# 09-DPLL-3.net
KiCad netlist of a schematic drawn in Altium Designer
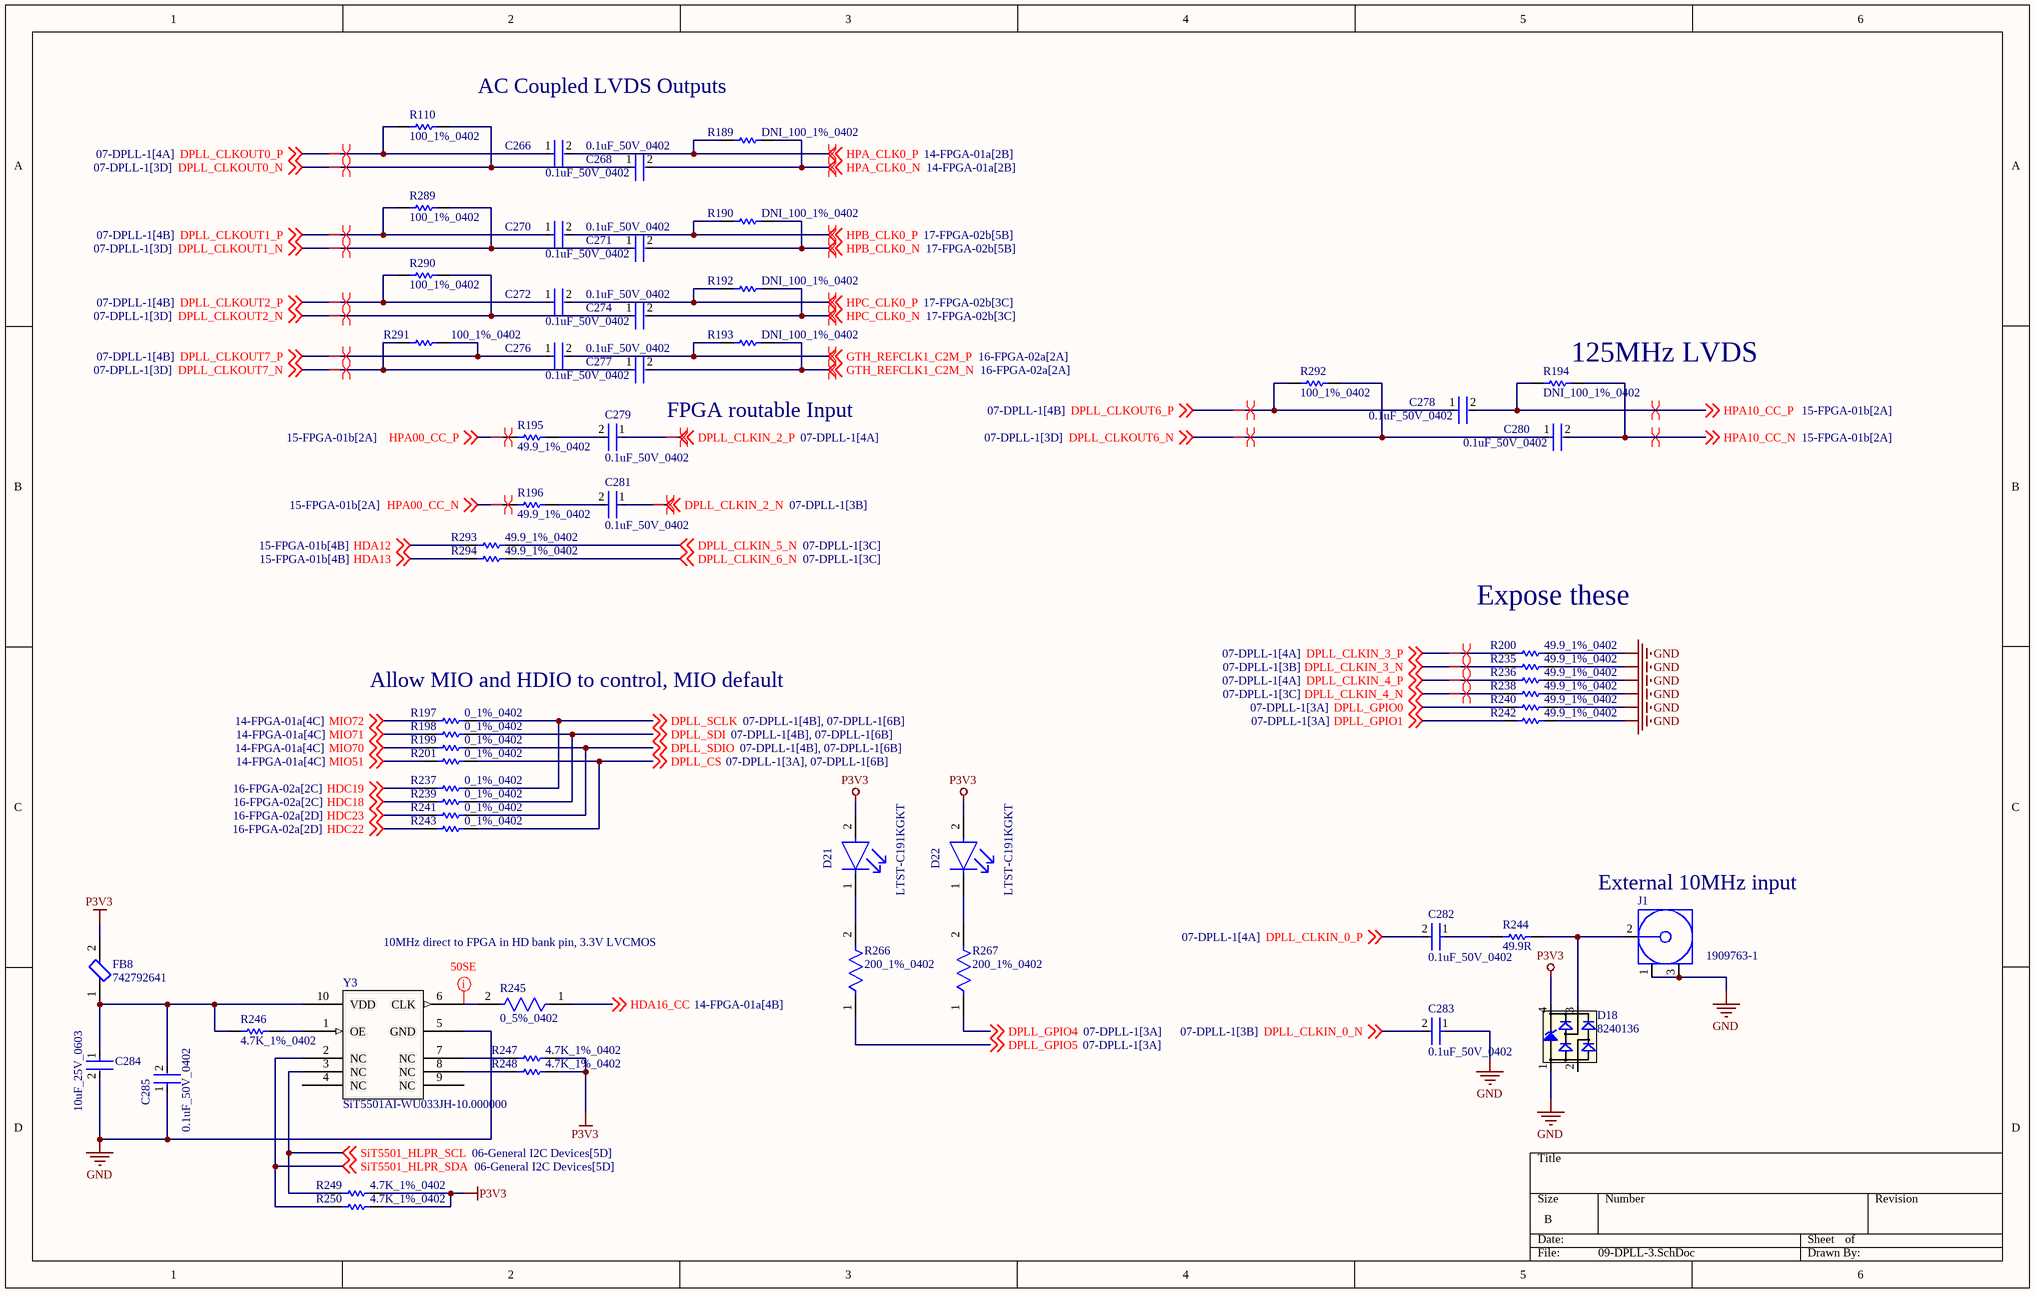
[diagram p0: 09-DPLL-3.SchDoc]

(export (version "E")
  (design (tool "Eeschema 10.0.6"))
  (components
    (comp (ref "C266")
      (value "0.1uF_50V_0402")
      (footprint "FP-C1005-050-0_05-IPC_C")
      (description "Multilayer Ceramic Capacitors 100nF ±10% 50V X7R SMD 0402")
      (fields (field (name "VOLTAGE") "50V") (field (name "TOLERANCE") "10%"))
      (libsource (lib "Altium Content Vault") (part "b4654b650e69147ec39a6b967a45e02"))
    )
    (comp (ref "C268")
      (value "0.1uF_50V_0402")
      (footprint "FP-C1005-050-0_05-IPC_C")
      (description "Multilayer Ceramic Capacitors 100nF ±10% 50V X7R SMD 0402")
      (fields (field (name "VOLTAGE") "50V") (field (name "TOLERANCE") "10%"))
      (libsource (lib "Altium Content Vault") (part "b4654b650e69147ec39a6b967a45e02"))
    )
    (comp (ref "C270")
      (value "0.1uF_50V_0402")
      (footprint "FP-C1005-050-0_05-IPC_C")
      (description "Multilayer Ceramic Capacitors 100nF ±10% 50V X7R SMD 0402")
      (fields (field (name "VOLTAGE") "50V") (field (name "TOLERANCE") "10%"))
      (libsource (lib "Altium Content Vault") (part "b4654b650e69147ec39a6b967a45e02"))
    )
    (comp (ref "C271")
      (value "0.1uF_50V_0402")
      (footprint "FP-C1005-050-0_05-IPC_C")
      (description "Multilayer Ceramic Capacitors 100nF ±10% 50V X7R SMD 0402")
      (fields (field (name "VOLTAGE") "50V") (field (name "TOLERANCE") "10%"))
      (libsource (lib "Altium Content Vault") (part "b4654b650e69147ec39a6b967a45e02"))
    )
    (comp (ref "C272")
      (value "0.1uF_50V_0402")
      (footprint "FP-C1005-050-0_05-IPC_C")
      (description "Multilayer Ceramic Capacitors 100nF ±10% 50V X7R SMD 0402")
      (fields (field (name "VOLTAGE") "50V") (field (name "TOLERANCE") "10%"))
      (libsource (lib "Altium Content Vault") (part "b4654b650e69147ec39a6b967a45e02"))
    )
    (comp (ref "C274")
      (value "0.1uF_50V_0402")
      (footprint "FP-C1005-050-0_05-IPC_C")
      (description "Multilayer Ceramic Capacitors 100nF ±10% 50V X7R SMD 0402")
      (fields (field (name "VOLTAGE") "50V") (field (name "TOLERANCE") "10%"))
      (libsource (lib "Altium Content Vault") (part "b4654b650e69147ec39a6b967a45e02"))
    )
    (comp (ref "C276")
      (value "0.1uF_50V_0402")
      (footprint "FP-C1005-050-0_05-IPC_C")
      (description "Multilayer Ceramic Capacitors 100nF ±10% 50V X7R SMD 0402")
      (fields (field (name "VOLTAGE") "50V") (field (name "TOLERANCE") "10%"))
      (libsource (lib "Altium Content Vault") (part "b4654b650e69147ec39a6b967a45e02"))
    )
    (comp (ref "C277")
      (value "0.1uF_50V_0402")
      (footprint "FP-C1005-050-0_05-IPC_C")
      (description "Multilayer Ceramic Capacitors 100nF ±10% 50V X7R SMD 0402")
      (fields (field (name "VOLTAGE") "50V") (field (name "TOLERANCE") "10%"))
      (libsource (lib "Altium Content Vault") (part "b4654b650e69147ec39a6b967a45e02"))
    )
    (comp (ref "C278")
      (value "0.1uF_50V_0402")
      (footprint "FP-C1005-050-0_05-IPC_C")
      (description "Multilayer Ceramic Capacitors 100nF ±10% 50V X7R SMD 0402")
      (fields (field (name "VOLTAGE") "50V") (field (name "TOLERANCE") "10%"))
      (libsource (lib "Altium Content Vault") (part "b4654b650e69147ec39a6b967a45e02"))
    )
    (comp (ref "C279")
      (value "0.1uF_50V_0402")
      (footprint "FP-C1005-050-0_05-IPC_C")
      (description "Multilayer Ceramic Capacitors 100nF ±10% 50V X7R SMD 0402")
      (fields (field (name "VOLTAGE") "50V") (field (name "TOLERANCE") "10%"))
      (libsource (lib "Altium Content Vault") (part "b4654b650e69147ec39a6b967a45e02"))
    )
    (comp (ref "C280")
      (value "0.1uF_50V_0402")
      (footprint "FP-C1005-050-0_05-IPC_C")
      (description "Multilayer Ceramic Capacitors 100nF ±10% 50V X7R SMD 0402")
      (fields (field (name "VOLTAGE") "50V") (field (name "TOLERANCE") "10%"))
      (libsource (lib "Altium Content Vault") (part "b4654b650e69147ec39a6b967a45e02"))
    )
    (comp (ref "C281")
      (value "0.1uF_50V_0402")
      (footprint "FP-C1005-050-0_05-IPC_C")
      (description "Multilayer Ceramic Capacitors 100nF ±10% 50V X7R SMD 0402")
      (fields (field (name "VOLTAGE") "50V") (field (name "TOLERANCE") "10%"))
      (libsource (lib "Altium Content Vault") (part "b4654b650e69147ec39a6b967a45e02"))
    )
    (comp (ref "C282")
      (value "0.1uF_50V_0402")
      (footprint "FP-C1005-050-0_05-IPC_C")
      (description "Multilayer Ceramic Capacitors 100nF ±10% 50V X7R SMD 0402")
      (fields (field (name "VOLTAGE") "50V") (field (name "TOLERANCE") "10%"))
      (libsource (lib "Altium Content Vault") (part "b4654b650e69147ec39a6b967a45e02"))
    )
    (comp (ref "C283")
      (value "0.1uF_50V_0402")
      (footprint "FP-C1005-050-0_05-IPC_C")
      (description "Multilayer Ceramic Capacitors 100nF ±10% 50V X7R SMD 0402")
      (fields (field (name "VOLTAGE") "50V") (field (name "TOLERANCE") "10%"))
      (libsource (lib "Altium Content Vault") (part "b4654b650e69147ec39a6b967a45e02"))
    )
    (comp (ref "C284")
      (value "10uF_25V_0603")
      (footprint "FP-CL10-IPC_C")
      (description "Cap Ceramic 10uF 25V X5R ±20% Pad SMD 0603 +85°C T/R")
      (fields (field (name "TOLERANCE") "20%"))
      (libsource (lib "Altium Content Vault") (part "b4654b650e69147ec39a6b967a45e02"))
    )
    (comp (ref "C285")
      (value "0.1uF_50V_0402")
      (footprint "FP-C1005-050-0_05-IPC_C")
      (description "Multilayer Ceramic Capacitors 100nF ±10% 50V X7R SMD 0402")
      (fields (field (name "VOLTAGE") "50V") (field (name "TOLERANCE") "10%"))
      (libsource (lib "Altium Content Vault") (part "b4654b650e69147ec39a6b967a45e02"))
    )
    (comp (ref "D18")
      (value "8240136")
      (footprint "SOT143-4L")
      (description "TVS Diode WE-TVS-HS, VRWM=3.3V")
      (fields (field (name "MANUFACTURER") "Wuerth Elektronik"))
      (libsource (lib "Altium Content Vault") (part "WE-TVS-HS-4"))
    )
    (comp (ref "D21")
      (value "LTST-C191KGKT")
      (footprint "FP-LTST-C191KGKT-MFG")
      (description "LED GREEN CLEAR SMD")
      (libsource (lib "Altium Content Vault") (part "8706943c75ba83719d021d2fdc84c58"))
    )
    (comp (ref "D22")
      (value "LTST-C191KGKT")
      (footprint "FP-LTST-C191KGKT-MFG")
      (description "LED GREEN CLEAR SMD")
      (libsource (lib "Altium Content Vault") (part "8706943c75ba83719d021d2fdc84c58"))
    )
    (comp (ref "FB8")
      (value "742792641")
      (footprint "FP-742792641-MFG")
      (description "FERRITE BEAD 300 OHM 0603 1LN")
      (fields (field (name "TOLERANCE") "25%"))
      (libsource (lib "Altium Content Vault") (part "5f30dd21d616792df468990f7003faa"))
    )
    (comp (ref "J1")
      (value "1909763-1")
      (footprint "TECO-1909763-1_V")
      (description "Ultra Miniature Coaxial Connector Jack, 60 V, 50 Ohm, -40 to 90 degC, RoHS, Tape and Reel")
      (fields (field (name "MANUFACTURER") "TE Connectivity"))
      (libsource (lib "Altium Content Vault") (part "CN-1P-M-RF3"))
    )
    (comp (ref "R110")
      (value "100_1%_0402")
      (footprint "RESC1005X40X25ML05T10")
      (fields (field (name "PART NUMBER") "ERJ-U02F1000X") (field (name "MANUFACTURER") "Panasonic"))
      (libsource (lib "Altium Content Vault") (part "RES"))
    )
    (comp (ref "R189")
      (value "DNI_100_1%_0402")
      (footprint "RESC1005X40X25LL05T05")
      (description "Chip Resistor, 100 Ohm, +/- 1%, 100 mW, -55 to 155 degC, 0402 (1005 Metric), RoHS, Tape and Reel")
      (fields (field (name "MANUFACTURER") "Basic Passives") (field (name "TOLERANCE") "1%"))
      (libsource (lib "Altium Content Vault") (part "RES-2"))
    )
    (comp (ref "R190")
      (value "DNI_100_1%_0402")
      (footprint "RESC1005X40X25LL05T05")
      (description "Chip Resistor, 100 Ohm, +/- 1%, 100 mW, -55 to 155 degC, 0402 (1005 Metric), RoHS, Tape and Reel")
      (fields (field (name "MANUFACTURER") "Basic Passives") (field (name "TOLERANCE") "1%"))
      (libsource (lib "Altium Content Vault") (part "RES-2"))
    )
    (comp (ref "R192")
      (value "DNI_100_1%_0402")
      (footprint "RESC1005X40X25LL05T05")
      (description "Chip Resistor, 100 Ohm, +/- 1%, 100 mW, -55 to 155 degC, 0402 (1005 Metric), RoHS, Tape and Reel")
      (fields (field (name "MANUFACTURER") "Basic Passives") (field (name "TOLERANCE") "1%"))
      (libsource (lib "Altium Content Vault") (part "RES-2"))
    )
    (comp (ref "R193")
      (value "DNI_100_1%_0402")
      (footprint "RESC1005X40X25LL05T05")
      (description "Chip Resistor, 100 Ohm, +/- 1%, 100 mW, -55 to 155 degC, 0402 (1005 Metric), RoHS, Tape and Reel")
      (fields (field (name "MANUFACTURER") "Basic Passives") (field (name "TOLERANCE") "1%"))
      (libsource (lib "Altium Content Vault") (part "RES-2"))
    )
    (comp (ref "R194")
      (value "DNI_100_1%_0402")
      (footprint "RESC1005X40X25ML05T10")
      (fields (field (name "PART NUMBER") "ERJ-U02F1000X") (field (name "MANUFACTURER") "Panasonic"))
      (libsource (lib "Altium Content Vault") (part "RES"))
    )
    (comp (ref "R195")
      (value "49.9_1%_0402")
      (footprint "RESC1005X40X25NL10T10")
      (fields (field (name "PART NUMBER") "RK73H1ETTP49R9F") (field (name "MANUFACTURER") "KOA Speer"))
      (libsource (lib "Altium Content Vault") (part "RES"))
    )
    (comp (ref "R196")
      (value "49.9_1%_0402")
      (footprint "RESC1005X40X25NL10T10")
      (fields (field (name "PART NUMBER") "RK73H1ETTP49R9F") (field (name "MANUFACTURER") "KOA Speer"))
      (libsource (lib "Altium Content Vault") (part "RES"))
    )
    (comp (ref "R197")
      (value "0_1%_0402")
      (footprint "RESC1005X40X25LL05T05")
      (description "Chip Resistor, 0 Ohm, 0.1 W, -55 to 155 degC, 0402 (1005 Metric), RoHS, Tape and Reel")
      (fields (field (name "MANUFACTURER") "Panasonic") (field (name "TOLERANCE") "5%"))
      (libsource (lib "Altium Content Vault") (part "RES-2"))
    )
    (comp (ref "R198")
      (value "0_1%_0402")
      (footprint "RESC1005X40X25LL05T05")
      (description "Chip Resistor, 0 Ohm, 0.1 W, -55 to 155 degC, 0402 (1005 Metric), RoHS, Tape and Reel")
      (fields (field (name "MANUFACTURER") "Panasonic") (field (name "TOLERANCE") "5%"))
      (libsource (lib "Altium Content Vault") (part "RES-2"))
    )
    (comp (ref "R199")
      (value "0_1%_0402")
      (footprint "RESC1005X40X25LL05T05")
      (description "Chip Resistor, 0 Ohm, 0.1 W, -55 to 155 degC, 0402 (1005 Metric), RoHS, Tape and Reel")
      (fields (field (name "MANUFACTURER") "Panasonic") (field (name "TOLERANCE") "5%"))
      (libsource (lib "Altium Content Vault") (part "RES-2"))
    )
    (comp (ref "R200")
      (value "49.9_1%_0402")
      (footprint "RESC1005X40X25NL10T10")
      (fields (field (name "PART NUMBER") "RK73H1ETTP49R9F") (field (name "MANUFACTURER") "KOA Speer"))
      (libsource (lib "Altium Content Vault") (part "RES"))
    )
    (comp (ref "R201")
      (value "0_1%_0402")
      (footprint "RESC1005X40X25LL05T05")
      (description "Chip Resistor, 0 Ohm, 0.1 W, -55 to 155 degC, 0402 (1005 Metric), RoHS, Tape and Reel")
      (fields (field (name "MANUFACTURER") "Panasonic") (field (name "TOLERANCE") "5%"))
      (libsource (lib "Altium Content Vault") (part "RES-2"))
    )
    (comp (ref "R235")
      (value "49.9_1%_0402")
      (footprint "RESC1005X40X25NL10T10")
      (fields (field (name "PART NUMBER") "RK73H1ETTP49R9F") (field (name "MANUFACTURER") "KOA Speer"))
      (libsource (lib "Altium Content Vault") (part "RES"))
    )
    (comp (ref "R236")
      (value "49.9_1%_0402")
      (footprint "RESC1005X40X25NL10T10")
      (fields (field (name "PART NUMBER") "RK73H1ETTP49R9F") (field (name "MANUFACTURER") "KOA Speer"))
      (libsource (lib "Altium Content Vault") (part "RES"))
    )
    (comp (ref "R237")
      (value "0_1%_0402")
      (footprint "RESC1005X40X25LL05T05")
      (description "Chip Resistor, 0 Ohm, 0.1 W, -55 to 155 degC, 0402 (1005 Metric), RoHS, Tape and Reel")
      (fields (field (name "MANUFACTURER") "Panasonic") (field (name "TOLERANCE") "5%"))
      (libsource (lib "Altium Content Vault") (part "RES-2"))
    )
    (comp (ref "R238")
      (value "49.9_1%_0402")
      (footprint "RESC1005X40X25NL10T10")
      (fields (field (name "PART NUMBER") "RK73H1ETTP49R9F") (field (name "MANUFACTURER") "KOA Speer"))
      (libsource (lib "Altium Content Vault") (part "RES"))
    )
    (comp (ref "R239")
      (value "0_1%_0402")
      (footprint "RESC1005X40X25LL05T05")
      (description "Chip Resistor, 0 Ohm, 0.1 W, -55 to 155 degC, 0402 (1005 Metric), RoHS, Tape and Reel")
      (fields (field (name "MANUFACTURER") "Panasonic") (field (name "TOLERANCE") "5%"))
      (libsource (lib "Altium Content Vault") (part "RES-2"))
    )
    (comp (ref "R240")
      (value "49.9_1%_0402")
      (footprint "RESC1005X40X25NL10T10")
      (fields (field (name "PART NUMBER") "RK73H1ETTP49R9F") (field (name "MANUFACTURER") "KOA Speer"))
      (libsource (lib "Altium Content Vault") (part "RES"))
    )
    (comp (ref "R241")
      (value "0_1%_0402")
      (footprint "RESC1005X40X25LL05T05")
      (description "Chip Resistor, 0 Ohm, 0.1 W, -55 to 155 degC, 0402 (1005 Metric), RoHS, Tape and Reel")
      (fields (field (name "MANUFACTURER") "Panasonic") (field (name "TOLERANCE") "5%"))
      (libsource (lib "Altium Content Vault") (part "RES-2"))
    )
    (comp (ref "R242")
      (value "49.9_1%_0402")
      (footprint "RESC1005X40X25NL10T10")
      (fields (field (name "PART NUMBER") "RK73H1ETTP49R9F") (field (name "MANUFACTURER") "KOA Speer"))
      (libsource (lib "Altium Content Vault") (part "RES"))
    )
    (comp (ref "R243")
      (value "0_1%_0402")
      (footprint "RESC1005X40X25LL05T05")
      (description "Chip Resistor, 0 Ohm, 0.1 W, -55 to 155 degC, 0402 (1005 Metric), RoHS, Tape and Reel")
      (fields (field (name "MANUFACTURER") "Panasonic") (field (name "TOLERANCE") "5%"))
      (libsource (lib "Altium Content Vault") (part "RES-2"))
    )
    (comp (ref "R244")
      (value "49.9R")
      (footprint "RESC1608X55X25NL10T15")
      (libsource (lib "Altium Content Vault") (part "RES-2"))
    )
    (comp (ref "R245")
      (value "0_5%_0402")
      (footprint "FP-AC0402-0_37-IPC_B")
      (description "RESISTOR 0402 JUMPER ZERO OHM")
      (fields (field (name "TOLERANCE") "1%"))
      (libsource (lib "Altium Content Vault") (part "1029c3af85768c4190bb7ad29bc67b5"))
    )
    (comp (ref "R246")
      (value "4.7K_1%_0402")
      (footprint "RESC1005X40X25NL10T10")
      (fields (field (name "MANUFACTURER") "Bourns") (field (name "PART NUMBER") "CR0402-FX-4701GLF"))
      (libsource (lib "Altium Content Vault") (part "RES"))
    )
    (comp (ref "R247")
      (value "4.7K_1%_0402")
      (footprint "RESC1005X40X25NL10T10")
      (fields (field (name "MANUFACTURER") "Bourns") (field (name "PART NUMBER") "CR0402-FX-4701GLF"))
      (libsource (lib "Altium Content Vault") (part "RES"))
    )
    (comp (ref "R248")
      (value "4.7K_1%_0402")
      (footprint "RESC1005X40X25NL10T10")
      (fields (field (name "MANUFACTURER") "Bourns") (field (name "PART NUMBER") "CR0402-FX-4701GLF"))
      (libsource (lib "Altium Content Vault") (part "RES"))
    )
    (comp (ref "R249")
      (value "4.7K_1%_0402")
      (footprint "RESC1005X40X25NL10T10")
      (fields (field (name "MANUFACTURER") "Bourns") (field (name "PART NUMBER") "CR0402-FX-4701GLF"))
      (libsource (lib "Altium Content Vault") (part "RES"))
    )
    (comp (ref "R250")
      (value "4.7K_1%_0402")
      (footprint "RESC1005X40X25NL10T10")
      (fields (field (name "MANUFACTURER") "Bourns") (field (name "PART NUMBER") "CR0402-FX-4701GLF"))
      (libsource (lib "Altium Content Vault") (part "RES"))
    )
    (comp (ref "R266")
      (value "200_1%_0402")
      (footprint "FP-ERJ2RK-IPC_A")
      (description "RES SMD 200 OHM 1% 1/10W 0402")
      (fields (field (name "TOLERANCE") "1%"))
      (libsource (lib "Altium Content Vault") (part "1029c3af85768c4190bb7ad29bc67b5"))
    )
    (comp (ref "R267")
      (value "200_1%_0402")
      (footprint "FP-ERJ2RK-IPC_A")
      (description "RES SMD 200 OHM 1% 1/10W 0402")
      (fields (field (name "TOLERANCE") "1%"))
      (libsource (lib "Altium Content Vault") (part "1029c3af85768c4190bb7ad29bc67b5"))
    )
    (comp (ref "R289")
      (value "100_1%_0402")
      (footprint "RESC1005X40X25ML05T10")
      (fields (field (name "PART NUMBER") "ERJ-U02F1000X") (field (name "MANUFACTURER") "Panasonic"))
      (libsource (lib "Altium Content Vault") (part "RES"))
    )
    (comp (ref "R290")
      (value "100_1%_0402")
      (footprint "RESC1005X40X25ML05T10")
      (fields (field (name "PART NUMBER") "ERJ-U02F1000X") (field (name "MANUFACTURER") "Panasonic"))
      (libsource (lib "Altium Content Vault") (part "RES"))
    )
    (comp (ref "R291")
      (value "100_1%_0402")
      (footprint "RESC1005X40X25ML05T10")
      (fields (field (name "PART NUMBER") "ERJ-U02F1000X") (field (name "MANUFACTURER") "Panasonic"))
      (libsource (lib "Altium Content Vault") (part "RES"))
    )
    (comp (ref "R292")
      (value "100_1%_0402")
      (footprint "RESC1005X40X25ML05T10")
      (fields (field (name "PART NUMBER") "ERJ-U02F1000X") (field (name "MANUFACTURER") "Panasonic"))
      (libsource (lib "Altium Content Vault") (part "RES"))
    )
    (comp (ref "R293")
      (value "49.9_1%_0402")
      (footprint "RESC1005X40X25NL10T10")
      (fields (field (name "PART NUMBER") "RK73H1ETTP49R9F") (field (name "MANUFACTURER") "KOA Speer"))
      (libsource (lib "Altium Content Vault") (part "RES"))
    )
    (comp (ref "R294")
      (value "49.9_1%_0402")
      (footprint "RESC1005X40X25NL10T10")
      (fields (field (name "PART NUMBER") "RK73H1ETTP49R9F") (field (name "MANUFACTURER") "KOA Speer"))
      (libsource (lib "Altium Content Vault") (part "RES"))
    )
    (comp (ref "Y3")
      (value "SiTime_SiT5501AC-WU-33E0-10T")
      (footprint "SITIME_SPL-086-CQFN-010-C07050_REV_DRAFT")
      (description "OSC, MEMS, STRATUM 3E, 10.000MHZ, 10PPB STAB, LVCMOS, 3.3V, O/P EN, 7.0X5.0X2.2MM, CQFN-10")
      (fields
        (field (name "MANUFACTURER PART NUMBER") "SiT5501AI-WU033JH-10.000000")
        (field (name "MANUFACTURER") "SiTime")
      )
      (libsource (lib "OCXO_DaughterCard") (part "CMP-OSC-00029-2"))
    )
  )
  (nets
    (net (code "1") (name "DPLL_CLKIN_0_N") (class "Default")
      (node (ref "C283") (pin "2") (pinfunction "2_2") (pintype "passive"))
    )
    (net (code "2") (name "DPLL_CLKIN_0_P") (class "Default")
      (node (ref "C282") (pin "2") (pinfunction "2_2") (pintype "passive"))
    )
    (net (code "3") (name "DPLL_CLKIN_2_N") (class "Default")
      (node (ref "C281") (pin "1") (pinfunction "1_1") (pintype "passive"))
    )
    (net (code "4") (name "DPLL_CLKIN_2_P") (class "Default")
      (node (ref "C279") (pin "1") (pinfunction "1_1") (pintype "passive"))
    )
    (net (code "5") (name "DPLL_CLKIN_3_N") (class "Default")
      (node (ref "R235") (pin "1") (pinfunction "1_1") (pintype "passive"))
    )
    (net (code "6") (name "DPLL_CLKIN_3_P") (class "Default")
      (node (ref "R200") (pin "1") (pinfunction "1_1") (pintype "passive"))
    )
    (net (code "7") (name "DPLL_CLKIN_4_N") (class "Default")
      (node (ref "R238") (pin "1") (pinfunction "1_1") (pintype "passive"))
    )
    (net (code "8") (name "DPLL_CLKIN_4_P") (class "Default")
      (node (ref "R236") (pin "1") (pinfunction "1_1") (pintype "passive"))
    )
    (net (code "9") (name "DPLL_CLKIN_5_N") (class "Default")
      (node (ref "R293") (pin "2") (pinfunction "2_2") (pintype "passive"))
    )
    (net (code "10") (name "DPLL_CLKIN_6_N") (class "Default")
      (node (ref "R294") (pin "2") (pinfunction "2_2") (pintype "passive"))
    )
    (net (code "11") (name "DPLL_CLKOUT0_N") (class "Default")
      (node (ref "C268") (pin "1") (pinfunction "1_1") (pintype "passive"))
      (node (ref "R110") (pin "2") (pinfunction "2_2") (pintype "passive"))
    )
    (net (code "12") (name "DPLL_CLKOUT0_P") (class "Default")
      (node (ref "C266") (pin "1") (pinfunction "1_1") (pintype "passive"))
      (node (ref "R110") (pin "1") (pinfunction "1_1") (pintype "passive"))
    )
    (net (code "13") (name "DPLL_CLKOUT1_N") (class "Default")
      (node (ref "C271") (pin "1") (pinfunction "1_1") (pintype "passive"))
      (node (ref "R289") (pin "2") (pinfunction "2_2") (pintype "passive"))
    )
    (net (code "14") (name "DPLL_CLKOUT1_P") (class "Default")
      (node (ref "C270") (pin "1") (pinfunction "1_1") (pintype "passive"))
      (node (ref "R289") (pin "1") (pinfunction "1_1") (pintype "passive"))
    )
    (net (code "15") (name "DPLL_CLKOUT2_N") (class "Default")
      (node (ref "C274") (pin "1") (pinfunction "1_1") (pintype "passive"))
      (node (ref "R290") (pin "2") (pinfunction "2_2") (pintype "passive"))
    )
    (net (code "16") (name "DPLL_CLKOUT2_P") (class "Default")
      (node (ref "C272") (pin "1") (pinfunction "1_1") (pintype "passive"))
      (node (ref "R290") (pin "1") (pinfunction "1_1") (pintype "passive"))
    )
    (net (code "17") (name "DPLL_CLKOUT6_N") (class "Default")
      (node (ref "C280") (pin "1") (pinfunction "1_1") (pintype "passive"))
      (node (ref "R292") (pin "2") (pinfunction "2_2") (pintype "passive"))
    )
    (net (code "18") (name "DPLL_CLKOUT6_P") (class "Default")
      (node (ref "C278") (pin "1") (pinfunction "1_1") (pintype "passive"))
      (node (ref "R292") (pin "1") (pinfunction "1_1") (pintype "passive"))
    )
    (net (code "19") (name "DPLL_CLKOUT7_N") (class "Default")
      (node (ref "C277") (pin "1") (pinfunction "1_1") (pintype "passive"))
      (node (ref "R291") (pin "1") (pinfunction "1_1") (pintype "passive"))
    )
    (net (code "20") (name "DPLL_CLKOUT7_P") (class "Default")
      (node (ref "C276") (pin "1") (pinfunction "1_1") (pintype "passive"))
      (node (ref "R291") (pin "2") (pinfunction "2_2") (pintype "passive"))
    )
    (net (code "21") (name "DPLL_CS") (class "Default")
      (node (ref "R201") (pin "2") (pinfunction "2_2") (pintype "passive"))
      (node (ref "R243") (pin "2") (pinfunction "2_2") (pintype "passive"))
    )
    (net (code "22") (name "DPLL_GPIO0") (class "Default")
      (node (ref "R240") (pin "1") (pinfunction "1_1") (pintype "passive"))
    )
    (net (code "23") (name "DPLL_GPIO1") (class "Default")
      (node (ref "R242") (pin "1") (pinfunction "1_1") (pintype "passive"))
    )
    (net (code "24") (name "DPLL_GPIO4") (class "Default")
      (node (ref "R267") (pin "1") (pinfunction "1_1") (pintype "passive"))
    )
    (net (code "25") (name "DPLL_GPIO5") (class "Default")
      (node (ref "R266") (pin "1") (pinfunction "1_1") (pintype "passive"))
    )
    (net (code "26") (name "DPLL_SCLK") (class "Default")
      (node (ref "R197") (pin "2") (pinfunction "2_2") (pintype "passive"))
      (node (ref "R237") (pin "2") (pinfunction "2_2") (pintype "passive"))
    )
    (net (code "27") (name "DPLL_SDI") (class "Default")
      (node (ref "R198") (pin "2") (pinfunction "2_2") (pintype "passive"))
      (node (ref "R239") (pin "2") (pinfunction "2_2") (pintype "passive"))
    )
    (net (code "28") (name "DPLL_SDIO") (class "Default")
      (node (ref "R199") (pin "2") (pinfunction "2_2") (pintype "passive"))
      (node (ref "R241") (pin "2") (pinfunction "2_2") (pintype "passive"))
    )
    (net (code "29") (name "GND") (class "Default")
      (node (ref "C283") (pin "1") (pinfunction "1_1") (pintype "passive"))
      (node (ref "C284") (pin "2") (pinfunction "2_2") (pintype "passive"))
      (node (ref "C285") (pin "1") (pinfunction "1_1") (pintype "passive"))
      (node (ref "D18") (pin "1") (pinfunction "GND_1") (pintype "passive"))
      (node (ref "J1") (pin "1") (pinfunction "1_1") (pintype "passive"))
      (node (ref "J1") (pin "3") (pinfunction "3_3") (pintype "passive"))
      (node (ref "R200") (pin "2") (pinfunction "2_2") (pintype "passive"))
      (node (ref "R235") (pin "2") (pinfunction "2_2") (pintype "passive"))
      (node (ref "R236") (pin "2") (pinfunction "2_2") (pintype "passive"))
      (node (ref "R238") (pin "2") (pinfunction "2_2") (pintype "passive"))
      (node (ref "R240") (pin "2") (pinfunction "2_2") (pintype "passive"))
      (node (ref "R242") (pin "2") (pinfunction "2_2") (pintype "passive"))
      (node (ref "Y3") (pin "5") (pinfunction "GND_5") (pintype "power_in"))
    )
    (net (code "30") (name "GTH_REFCLK1_C2M_N") (class "Default")
      (node (ref "C277") (pin "2") (pinfunction "2_2") (pintype "passive"))
      (node (ref "R193") (pin "2") (pinfunction "2_2") (pintype "passive"))
    )
    (net (code "31") (name "GTH_REFCLK1_C2M_P") (class "Default")
      (node (ref "C276") (pin "2") (pinfunction "2_2") (pintype "passive"))
      (node (ref "R193") (pin "1") (pinfunction "1_1") (pintype "passive"))
    )
    (net (code "32") (name "HDA12") (class "Default")
      (node (ref "R293") (pin "1") (pinfunction "1_1") (pintype "passive"))
    )
    (net (code "33") (name "HDA13") (class "Default")
      (node (ref "R294") (pin "1") (pinfunction "1_1") (pintype "passive"))
    )
    (net (code "34") (name "HDA16_CC") (class "Default")
      (node (ref "R245") (pin "1") (pinfunction "1_1") (pintype "passive"))
    )
    (net (code "35") (name "HDC18") (class "Default")
      (node (ref "R239") (pin "1") (pinfunction "1_1") (pintype "passive"))
    )
    (net (code "36") (name "HDC19") (class "Default")
      (node (ref "R237") (pin "1") (pinfunction "1_1") (pintype "passive"))
    )
    (net (code "37") (name "HDC22") (class "Default")
      (node (ref "R243") (pin "1") (pinfunction "1_1") (pintype "passive"))
    )
    (net (code "38") (name "HDC23") (class "Default")
      (node (ref "R241") (pin "1") (pinfunction "1_1") (pintype "passive"))
    )
    (net (code "39") (name "HPA00_CC_N") (class "Default")
      (node (ref "R196") (pin "1") (pinfunction "1_1") (pintype "passive"))
    )
    (net (code "40") (name "HPA00_CC_P") (class "Default")
      (node (ref "R195") (pin "1") (pinfunction "1_1") (pintype "passive"))
    )
    (net (code "41") (name "HPA10_CC_N") (class "Default")
      (node (ref "C280") (pin "2") (pinfunction "2_2") (pintype "passive"))
      (node (ref "R194") (pin "2") (pinfunction "2_2") (pintype "passive"))
    )
    (net (code "42") (name "HPA10_CC_P") (class "Default")
      (node (ref "C278") (pin "2") (pinfunction "2_2") (pintype "passive"))
      (node (ref "R194") (pin "1") (pinfunction "1_1") (pintype "passive"))
    )
    (net (code "43") (name "HPA_CLK0_N") (class "Default")
      (node (ref "C268") (pin "2") (pinfunction "2_2") (pintype "passive"))
      (node (ref "R189") (pin "2") (pinfunction "2_2") (pintype "passive"))
    )
    (net (code "44") (name "HPA_CLK0_P") (class "Default")
      (node (ref "C266") (pin "2") (pinfunction "2_2") (pintype "passive"))
      (node (ref "R189") (pin "1") (pinfunction "1_1") (pintype "passive"))
    )
    (net (code "45") (name "HPB_CLK0_N") (class "Default")
      (node (ref "C271") (pin "2") (pinfunction "2_2") (pintype "passive"))
      (node (ref "R190") (pin "2") (pinfunction "2_2") (pintype "passive"))
    )
    (net (code "46") (name "HPB_CLK0_P") (class "Default")
      (node (ref "C270") (pin "2") (pinfunction "2_2") (pintype "passive"))
      (node (ref "R190") (pin "1") (pinfunction "1_1") (pintype "passive"))
    )
    (net (code "47") (name "HPC_CLK0_N") (class "Default")
      (node (ref "C274") (pin "2") (pinfunction "2_2") (pintype "passive"))
      (node (ref "R192") (pin "2") (pinfunction "2_2") (pintype "passive"))
    )
    (net (code "48") (name "HPC_CLK0_P") (class "Default")
      (node (ref "C272") (pin "2") (pinfunction "2_2") (pintype "passive"))
      (node (ref "R192") (pin "1") (pinfunction "1_1") (pintype "passive"))
    )
    (net (code "49") (name "MIO51") (class "Default")
      (node (ref "R201") (pin "1") (pinfunction "1_1") (pintype "passive"))
    )
    (net (code "50") (name "MIO70") (class "Default")
      (node (ref "R199") (pin "1") (pinfunction "1_1") (pintype "passive"))
    )
    (net (code "51") (name "MIO71") (class "Default")
      (node (ref "R198") (pin "1") (pinfunction "1_1") (pintype "passive"))
    )
    (net (code "52") (name "MIO72") (class "Default")
      (node (ref "R197") (pin "1") (pinfunction "1_1") (pintype "passive"))
    )
    (net (code "53") (name "Net-(C279-Pad2)") (class "Default")
      (node (ref "C279") (pin "2") (pinfunction "2_2") (pintype "passive"))
      (node (ref "R195") (pin "2") (pinfunction "2_2") (pintype "passive"))
    )
    (net (code "54") (name "Net-(C281-Pad2)") (class "Default")
      (node (ref "C281") (pin "2") (pinfunction "2_2") (pintype "passive"))
      (node (ref "R196") (pin "2") (pinfunction "2_2") (pintype "passive"))
    )
    (net (code "55") (name "Net-(C282-Pad1)") (class "Default")
      (node (ref "C282") (pin "1") (pinfunction "1_1") (pintype "passive"))
      (node (ref "R244") (pin "1") (pinfunction "1_1") (pintype "passive"))
    )
    (net (code "56") (name "Net-(D18-I{slash}O2)") (class "Default")
      (node (ref "D18") (pin "3") (pinfunction "I/O2_3") (pintype "passive"))
      (node (ref "J1") (pin "2") (pinfunction "2_2") (pintype "passive"))
      (node (ref "R244") (pin "2") (pinfunction "2_2") (pintype "passive"))
    )
    (net (code "57") (name "Net-(D21-C)") (class "Default")
      (node (ref "D21") (pin "1") (pinfunction "C_1") (pintype "passive"))
      (node (ref "R266") (pin "2") (pinfunction "2_2") (pintype "passive"))
    )
    (net (code "58") (name "Net-(D22-C)") (class "Default")
      (node (ref "D22") (pin "1") (pinfunction "C_1") (pintype "passive"))
      (node (ref "R267") (pin "2") (pinfunction "2_2") (pintype "passive"))
    )
    (net (code "59") (name "Net-(R247-Pad1)") (class "Default")
      (node (ref "R247") (pin "1") (pinfunction "1_1") (pintype "passive"))
      (node (ref "Y3") (pin "7") (pinfunction "NC_7") (pintype "passive"))
    )
    (net (code "60") (name "Net-(R248-Pad1)") (class "Default")
      (node (ref "R248") (pin "1") (pinfunction "1_1") (pintype "passive"))
      (node (ref "Y3") (pin "8") (pinfunction "NC_8") (pintype "passive"))
    )
    (net (code "61") (name "Net-(Y3-CLK)") (class "Default")
      (node (ref "R245") (pin "2") (pinfunction "2_2") (pintype "passive"))
      (node (ref "Y3") (pin "6") (pinfunction "CLK_6") (pintype "output"))
    )
    (net (code "62") (name "Net-(Y3-OE)") (class "Default")
      (node (ref "R246") (pin "1") (pinfunction "1_1") (pintype "passive"))
      (node (ref "Y3") (pin "1") (pinfunction "OE_1") (pintype "input"))
    )
    (net (code "63") (name "Net-(Y3-VDD)") (class "Default")
      (node (ref "C284") (pin "1") (pinfunction "1_1") (pintype "passive"))
      (node (ref "C285") (pin "2") (pinfunction "2_2") (pintype "passive"))
      (node (ref "FB8") (pin "1") (pinfunction "1_1") (pintype "passive"))
      (node (ref "R246") (pin "2") (pinfunction "2_2") (pintype "passive"))
      (node (ref "Y3") (pin "10") (pinfunction "VDD_10") (pintype "power_in"))
    )
    (net (code "64") (name "P3V3") (class "Default")
      (node (ref "D18") (pin "4") (pinfunction "VDD_4") (pintype "passive"))
      (node (ref "D21") (pin "2") (pinfunction "A_2") (pintype "passive"))
      (node (ref "D22") (pin "2") (pinfunction "A_2") (pintype "passive"))
      (node (ref "FB8") (pin "2") (pinfunction "2_2") (pintype "passive"))
      (node (ref "R247") (pin "2") (pinfunction "2_2") (pintype "passive"))
      (node (ref "R248") (pin "2") (pinfunction "2_2") (pintype "passive"))
      (node (ref "R249") (pin "2") (pinfunction "2_2") (pintype "passive"))
      (node (ref "R250") (pin "2") (pinfunction "2_2") (pintype "passive"))
    )
    (net (code "65") (name "SiT5501_HLPR_SCL") (class "Default")
      (node (ref "R249") (pin "1") (pinfunction "1_1") (pintype "passive"))
      (node (ref "Y3") (pin "3") (pinfunction "NC_3") (pintype "passive"))
    )
    (net (code "66") (name "SiT5501_HLPR_SDA") (class "Default")
      (node (ref "R250") (pin "1") (pinfunction "1_1") (pintype "passive"))
      (node (ref "Y3") (pin "2") (pinfunction "NC_2") (pintype "passive"))
    )
    (net (code "67") (name "unconnected-(D18-I{slash}O1-Pad2)") (class "Default")
      (node (ref "D18") (pin "2") (pinfunction "I/O1_2") (pintype "passive"))
    )
    (net (code "68") (name "unconnected-(Y3-NC-Pad4)") (class "Default")
      (node (ref "Y3") (pin "4") (pinfunction "NC_4") (pintype "passive"))
    )
    (net (code "69") (name "unconnected-(Y3-NC-Pad9)") (class "Default")
      (node (ref "Y3") (pin "9") (pinfunction "NC_9") (pintype "passive"))
    )
  )
)
